# power.net
KiCad netlist of a schematic drawn in Altium Designer
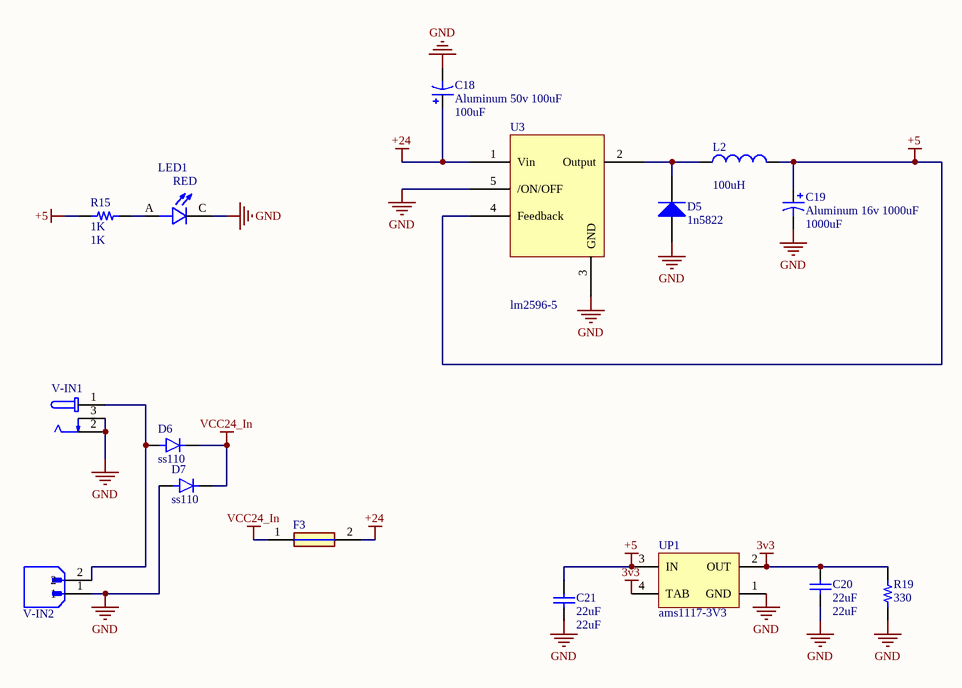
[diagram p0: power.SchDoc]

(export (version "E")
  (design (tool "Eeschema 10.0.6"))
  (components
    (comp (ref "C18")
      (value "Aluminum 50v 100uF")
      (footprint "Cap SMD 100UF 35~50v")
      (description "CAP POLAR SMD")
      (fields (field (name "ALTIUM_VALUE") "100uF") (field (name "PUBLISHER") "Altium Limited"))
      (libsource (lib "Miscellaneous Devices") (part "Cap Pol1"))
    )
    (comp (ref "C19")
      (value "Aluminum 16v 1000uF")
      (footprint "CAP SMD 1000UF 16V")
      (description "CAP POLAR SMD")
      (fields (field (name "ALTIUM_VALUE") "1000uF") (field (name "PUBLISHER") "Altium Limited"))
      (libsource (lib "Miscellaneous Devices") (part "Cap Pol1"))
    )
    (comp (ref "C20")
      (value "22uF")
      (footprint "0603C")
      (description "CAP SMD 0603")
      (fields (field (name "ALTIUM_VALUE") "22uF") (field (name "PUBLISHER") "Altium Limited"))
      (libsource (lib "Miscellaneous Devices") (part "Cap"))
    )
    (comp (ref "C21")
      (value "22uF")
      (footprint "0603C")
      (description "CAP SMD 0603")
      (fields (field (name "ALTIUM_VALUE") "22uF") (field (name "PUBLISHER") "Altium Limited"))
      (libsource (lib "Miscellaneous Devices") (part "Cap"))
    )
    (comp (ref "D5")
      (value "1n5822")
      (footprint "SMA DIODE 2")
      (description "1 Amp schottky Diode SMA")
      (fields (field (name "PUBLISHER") "Altium Limited"))
      (libsource (lib "Miscellaneous Devices") (part "Diode 1N4007"))
    )
    (comp (ref "D6")
      (value "ss110")
      (footprint "ss110")
      (description "Diode Super Barrier 60V 500mA Surface Mount SOD-123")
      (fields (field (name "MP") "SBR0560S1-7") (field (name "MF") "Diodes Inc."))
      (libsource (lib "diode") (part "SBR0560S1-7"))
    )
    (comp (ref "D7")
      (value "ss110")
      (footprint "ss110")
      (description "Diode Super Barrier 60V 500mA Surface Mount SOD-123")
      (fields (field (name "MP") "SBR0560S1-7") (field (name "MF") "Diodes Inc."))
      (libsource (lib "diode") (part "SBR0560S1-7"))
    )
    (comp (ref "F3")
      (value "fuse 2amp")
      (footprint "1206 FUSE")
      (description "Fuse 1206")
      (fields (field (name "MANUFACTURER_PART_NUMBER") "1206SFS200F/63-2"))
      (libsource (lib "robot1") (part "1206SFS200F_63-2"))
    )
    (comp (ref "L2")
      (value "100uH")
      (footprint "inductor")
      (description "Inductor 12*12mm")
      (fields (field (name "Comment") "inductor 100uH") (field (name "PUBLISHER") "Altium Limited"))
      (libsource (lib "Miscellaneous Devices") (part "Inductor"))
    )
    (comp (ref "LED1")
      (value "LED RED")
      (footprint "LED_7012X1")
      (description "LED SMD 0805 RED")
      (fields (field (name "MP") "7012X1"))
      (libsource (lib "LED0805") (part "7012X1"))
    )
    (comp (ref "R15")
      (value "1K")
      (footprint "0603R")
      (description "RES SMD 0603")
      (fields (field (name "PART NUMBER") "RCS0805100KFKEA") (field (name "ALTIUM_VALUE") "1K"))
      (libsource (lib "lamp control-ver2") (part "Resistor"))
    )
    (comp (ref "R19")
      (value "330")
      (footprint "0603R")
      (description "RES SMD 0603")
      (fields (field (name "PART NUMBER") "RCS0805100KFKEA"))
      (libsource (lib "lamp control-ver2") (part "Resistor"))
    )
    (comp (ref "U3") (value "lm2596-5") (footprint "2596") (libsource (lib "No.2") (part "lm2596")))
    (comp (ref "UP1")
      (value "ams1117-3V3")
      (footprint "SOT223")
      (description "3.3 Volt, 800mA SOT-223")
      (fields (field (name "DESIGNER") "Ali Hafizi"))
      (libsource (lib "Altium (2)") (part "AMS1117-x.x"))
    )
    (comp (ref "V-IN1")
      (value "DC jack power")
      (footprint "GCT_DCJ235-05-A-XX-X_REVA")
      (description "Dc Power Jack on-board")
      (fields (field (name "MF") "Global Connector Technology") (field (name "MP") "DCJ235-05-A-K1-A"))
      (libsource (lib "DCJ235-05-A-XX-X_REVA") (part "DCJ235-05-A-XX-X_REVA"))
    )
    (comp (ref "V-IN2")
      (value "Phoenix")
      (footprint "AMPHENOL_OQ0271510000G")
      (description "Phoenix Terminal Right 2PIN")
      (fields (field (name "MP") "OQ0271510000G") (field (name "MF") "Amphenol Anytek"))
      (libsource (lib "phoenix2") (part "OQ0271510000G"))
    )
  )
  (nets
    (net (code "1") (name "+5") (class "Default")
      (node (ref "C19") (pin "1") (pinfunction "1_1") (pintype "passive"))
      (node (ref "C21") (pin "2") (pinfunction "2_2") (pintype "passive"))
      (node (ref "L2") (pin "2") (pinfunction "2_2") (pintype "passive"))
      (node (ref "R15") (pin "1") (pinfunction "1_1") (pintype "passive"))
      (node (ref "U3") (pin "4") (pinfunction "Feedback_4") (pintype "power_in"))
      (node (ref "UP1") (pin "3") (pinfunction "IN_3") (pintype "power_in"))
    )
    (net (code "2") (name "+24") (class "Default")
      (node (ref "C18") (pin "1") (pinfunction "1_1") (pintype "passive"))
      (node (ref "F3") (pin "2") (pinfunction "2_2") (pintype "passive"))
      (node (ref "U3") (pin "1") (pinfunction "Vin_1") (pintype "power_in"))
    )
    (net (code "3") (name "3v3") (class "Default")
      (node (ref "C20") (pin "2") (pinfunction "2_2") (pintype "passive"))
      (node (ref "R19") (pin "1") (pinfunction "1_1") (pintype "passive"))
      (node (ref "UP1") (pin "2") (pinfunction "OUT_2") (pintype "power_in"))
      (node (ref "UP1") (pin "4") (pinfunction "TAB_4") (pintype "power_in"))
    )
    (net (code "4") (name "GND") (class "Default")
      (node (ref "C18") (pin "2") (pinfunction "2_2") (pintype "passive"))
      (node (ref "C19") (pin "2") (pinfunction "2_2") (pintype "passive"))
      (node (ref "C20") (pin "1") (pinfunction "1_1") (pintype "passive"))
      (node (ref "C21") (pin "1") (pinfunction "1_1") (pintype "passive"))
      (node (ref "D5") (pin "1") (pinfunction "A_1") (pintype "passive"))
      (node (ref "D7") (pin "A") (pinfunction "A_A") (pintype "passive"))
      (node (ref "LED1") (pin "C") (pinfunction "C_C") (pintype "passive"))
      (node (ref "R19") (pin "2") (pinfunction "2_2") (pintype "passive"))
      (node (ref "U3") (pin "3") (pinfunction "GND_3") (pintype "power_in"))
      (node (ref "U3") (pin "5") (pinfunction "/ON/OFF_5") (pintype "power_in"))
      (node (ref "UP1") (pin "1") (pinfunction "GND_1") (pintype "power_in"))
      (node (ref "V-IN1") (pin "2") (pinfunction "2_2") (pintype "passive"))
      (node (ref "V-IN1") (pin "3") (pinfunction "3_3") (pintype "passive"))
      (node (ref "V-IN2") (pin "1") (pinfunction "1_1") (pintype "passive"))
    )
    (net (code "5") (name "Net-(D5-K)") (class "Default")
      (node (ref "D5") (pin "2") (pinfunction "K_2") (pintype "passive"))
      (node (ref "L2") (pin "1") (pinfunction "1_1") (pintype "passive"))
      (node (ref "U3") (pin "2") (pinfunction "Output_2") (pintype "power_in"))
    )
    (net (code "6") (name "Net-(D6-PadA)") (class "Default")
      (node (ref "D6") (pin "A") (pinfunction "A_A") (pintype "passive"))
      (node (ref "V-IN1") (pin "1") (pinfunction "1_1") (pintype "passive"))
      (node (ref "V-IN2") (pin "2") (pinfunction "2_2") (pintype "passive"))
    )
    (net (code "7") (name "Net-(LED1-PadA)") (class "Default")
      (node (ref "LED1") (pin "A") (pinfunction "A_A") (pintype "passive"))
      (node (ref "R15") (pin "2") (pinfunction "2_2") (pintype "passive"))
    )
    (net (code "8") (name "VCC24_In") (class "Default")
      (node (ref "D6") (pin "C") (pinfunction "K_C") (pintype "passive"))
      (node (ref "D7") (pin "C") (pinfunction "K_C") (pintype "passive"))
      (node (ref "F3") (pin "1") (pinfunction "1_1") (pintype "passive"))
    )
  )
)
